# Peripherals.net
KiCad netlist of a schematic drawn in Altium Designer
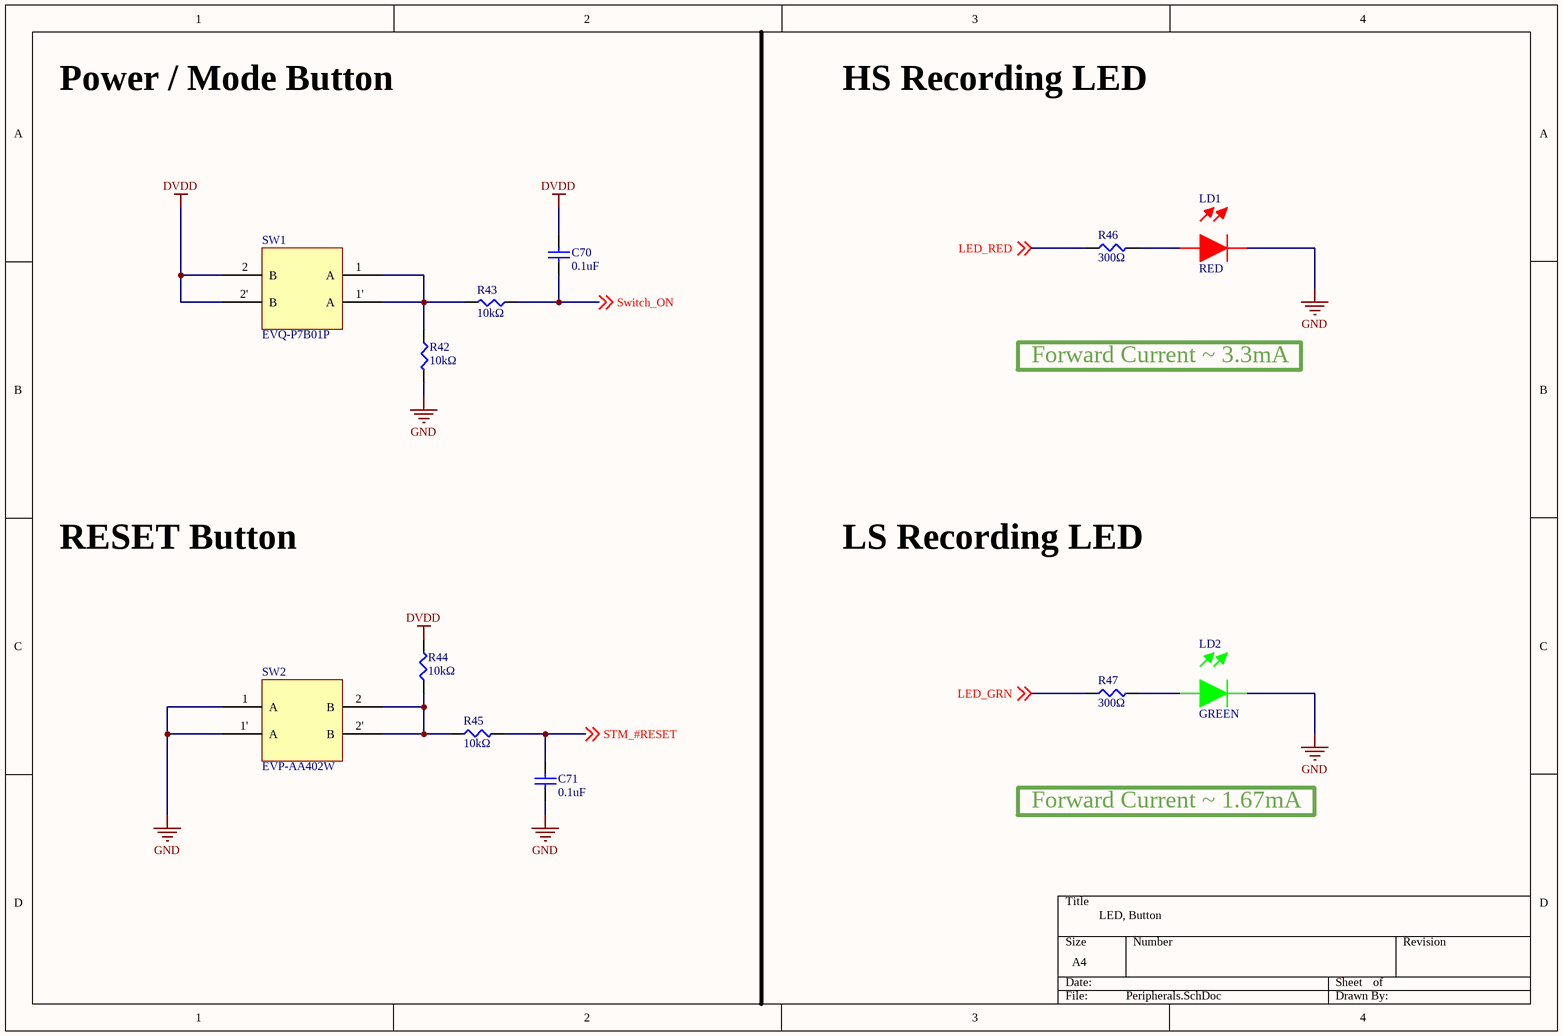
[diagram p0: Peripherals.SchDoc]

(export (version "E")
  (design (tool "Eeschema 10.0.6"))
  (components
    (comp (ref "C70")
      (value "0.1uF")
      (footprint "0402")
      (description "MLCC-0402")
      (libsource (lib "MLCC") (part "0402"))
    )
    (comp (ref "C71")
      (value "0.1uF")
      (footprint "0402")
      (description "MLCC-0402")
      (libsource (lib "MLCC") (part "0402"))
    )
    (comp (ref "LD1") (value "RED") (footprint "RED") (libsource (lib "LED") (part "RED")))
    (comp (ref "LD2") (value "GREEN") (footprint "GREEN") (libsource (lib "LED") (part "GREEN")))
    (comp (ref "R42")
      (value "10kΩ")
      (footprint "0402")
      (description "Resistor_SMD_0402")
      (fields (field (name "AUTHORBY") "yjlab"))
      (libsource (lib "Resistor") (part "0402"))
    )
    (comp (ref "R43")
      (value "10kΩ")
      (footprint "0402")
      (description "Resistor_SMD_0402")
      (fields (field (name "AUTHORBY") "yjlab"))
      (libsource (lib "Resistor") (part "0402"))
    )
    (comp (ref "R44")
      (value "10kΩ")
      (footprint "0402")
      (description "Resistor_SMD_0402")
      (fields (field (name "AUTHORBY") "yjlab"))
      (libsource (lib "Resistor") (part "0402"))
    )
    (comp (ref "R45")
      (value "10kΩ")
      (footprint "0402")
      (description "Resistor_SMD_0402")
      (fields (field (name "AUTHORBY") "yjlab"))
      (libsource (lib "Resistor") (part "0402"))
    )
    (comp (ref "R46")
      (value "300Ω")
      (footprint "0402")
      (description "Resistor_SMD_0402")
      (fields (field (name "AUTHORBY") "yjlab"))
      (libsource (lib "Resistor") (part "0402"))
    )
    (comp (ref "R47")
      (value "300Ω")
      (footprint "0402")
      (description "Resistor_SMD_0402")
      (fields (field (name "AUTHORBY") "yjlab"))
      (libsource (lib "Resistor") (part "0402"))
    )
    (comp (ref "SW1")
      (value "EVQ-P7B01P")
      (footprint "2.2N")
      (description "Light Touch Switch, Right Angle, Operating Force 2.2 (N)")
      (libsource (lib "EVQP7xxxP") (part "EVQ-P7B01P"))
    )
    (comp (ref "SW2")
      (value "EVP-AA402W")
      (footprint "2.4N")
      (description "Lite Touch Switch, Vertical, Operating Force 2.4(N)")
      (libsource (lib "EVPAAx02x") (part "EVP-AA402W"))
    )
  )
  (nets
    (net (code "1") (name "DVDD") (class "Default")
      (node (ref "C70") (pin "1") (pinfunction "1_1") (pintype "passive"))
      (node (ref "R44") (pin "2") (pinfunction "2_2") (pintype "passive"))
      (node (ref "SW1") (pin "2") (pinfunction "B_2") (pintype "passive"))
      (node (ref "SW1") (pin "2'") (pinfunction "B_2'") (pintype "passive"))
    )
    (net (code "2") (name "GND") (class "Default")
      (node (ref "C71") (pin "1") (pinfunction "1_1") (pintype "passive"))
      (node (ref "LD1") (pin "C") (pinfunction "C_C") (pintype "passive"))
      (node (ref "LD2") (pin "C") (pinfunction "C_C") (pintype "passive"))
      (node (ref "R42") (pin "2") (pinfunction "2_2") (pintype "passive"))
      (node (ref "SW2") (pin "1") (pinfunction "A_1") (pintype "passive"))
      (node (ref "SW2") (pin "1'") (pinfunction "A_1'") (pintype "passive"))
    )
    (net (code "3") (name "LED_GRN") (class "Default")
      (node (ref "R47") (pin "1") (pinfunction "1_1") (pintype "passive"))
    )
    (net (code "4") (name "LED_RED") (class "Default")
      (node (ref "R46") (pin "1") (pinfunction "1_1") (pintype "passive"))
    )
    (net (code "5") (name "Net-(LD1-PadA)") (class "Default")
      (node (ref "LD1") (pin "A") (pinfunction "A_A") (pintype "passive"))
      (node (ref "R46") (pin "2") (pinfunction "2_2") (pintype "passive"))
    )
    (net (code "6") (name "Net-(LD2-PadA)") (class "Default")
      (node (ref "LD2") (pin "A") (pinfunction "A_A") (pintype "passive"))
      (node (ref "R47") (pin "2") (pinfunction "2_2") (pintype "passive"))
    )
    (net (code "7") (name "Net-(R42-Pad1)") (class "Default")
      (node (ref "R42") (pin "1") (pinfunction "1_1") (pintype "passive"))
      (node (ref "R43") (pin "2") (pinfunction "2_2") (pintype "passive"))
      (node (ref "SW1") (pin "1") (pinfunction "A_1") (pintype "passive"))
      (node (ref "SW1") (pin "1'") (pinfunction "A_1'") (pintype "passive"))
    )
    (net (code "8") (name "Net-(R44-Pad1)") (class "Default")
      (node (ref "R44") (pin "1") (pinfunction "1_1") (pintype "passive"))
      (node (ref "R45") (pin "1") (pinfunction "1_1") (pintype "passive"))
      (node (ref "SW2") (pin "2") (pinfunction "B_2") (pintype "passive"))
      (node (ref "SW2") (pin "2'") (pinfunction "B_2'") (pintype "passive"))
    )
    (net (code "9") (name "STM_#RESET") (class "Default")
      (node (ref "C71") (pin "2") (pinfunction "2_2") (pintype "passive"))
      (node (ref "R45") (pin "2") (pinfunction "2_2") (pintype "passive"))
    )
    (net (code "10") (name "Switch_ON") (class "Default")
      (node (ref "C70") (pin "2") (pinfunction "2_2") (pintype "passive"))
      (node (ref "R43") (pin "1") (pinfunction "1_1") (pintype "passive"))
    )
  )
)
